# main35.net
KiCad netlist of a schematic drawn in EAGLE
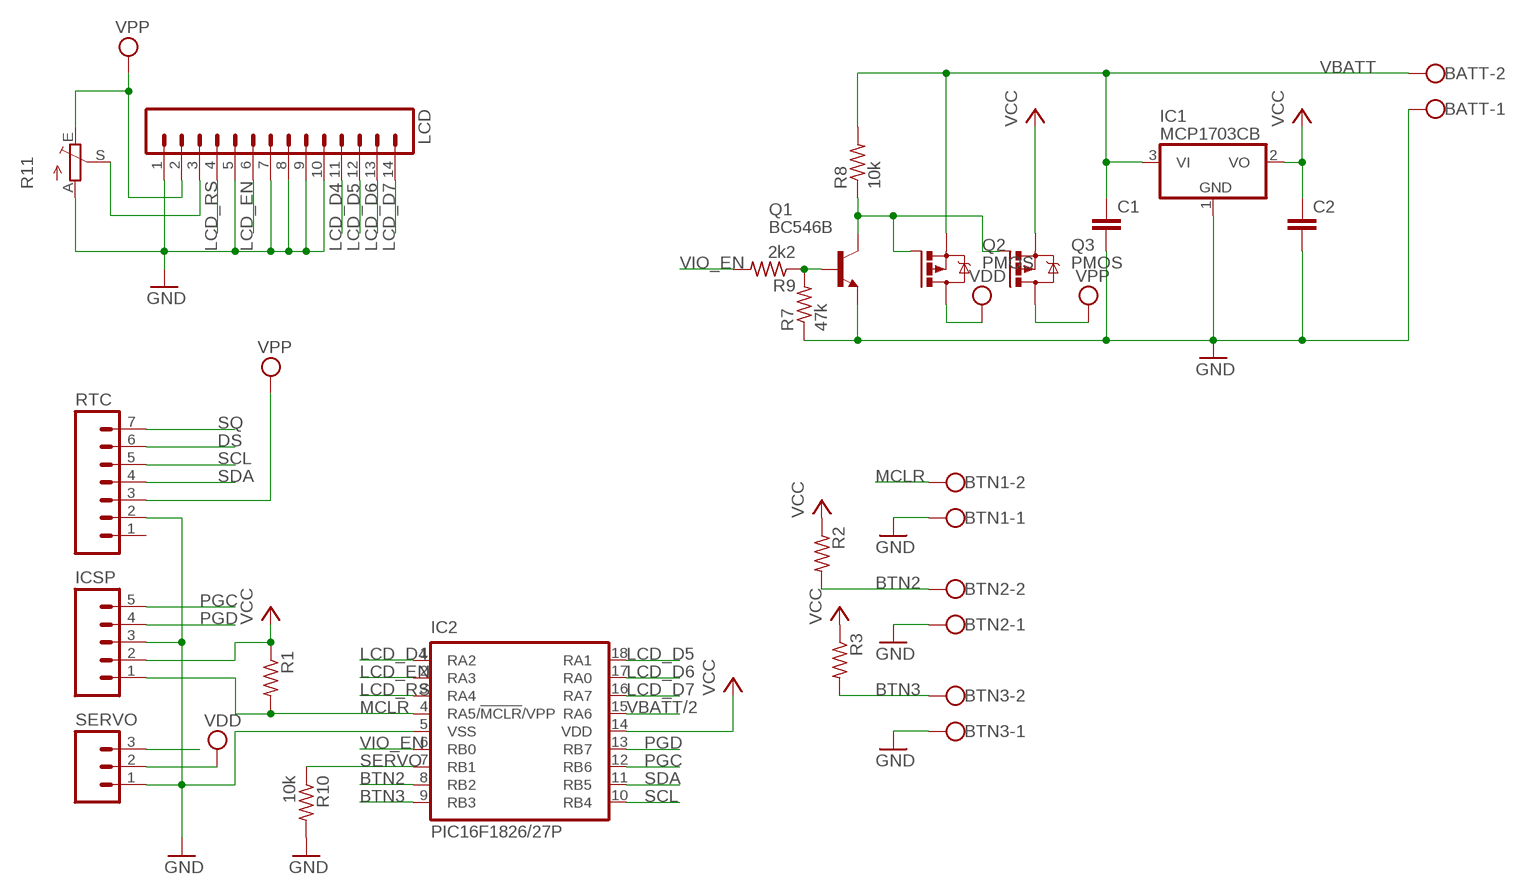
[diagram p0: schematic, sheet 1]

(export (version "E")
  (design (tool "Eeschema 10.0.6"))
  (components
    (comp (ref "BATT")
      (value "W237-102")
      (footprint "eagle-import:W237-102")
      (fields (field (name "MPN") "237-102"))
      (libsource (lib "eagle-import") (part "W237-102"))
    )
    (comp (ref "BTN1")
      (value "W237-102")
      (footprint "eagle-import:W237-102")
      (fields (field (name "MPN") "237-102"))
      (libsource (lib "eagle-import") (part "W237-102"))
    )
    (comp (ref "BTN2")
      (value "W237-102")
      (footprint "eagle-import:W237-102")
      (fields (field (name "MPN") "237-102"))
      (libsource (lib "eagle-import") (part "W237-102"))
    )
    (comp (ref "BTN3")
      (value "W237-102")
      (footprint "eagle-import:W237-102")
      (fields (field (name "MPN") "237-102"))
      (libsource (lib "eagle-import") (part "W237-102"))
    )
    (comp (ref "C1")
      (value "C-EUC0805K")
      (footprint "eagle-import:C0805K")
      (libsource (lib "eagle-import") (part "C-EUC0805K"))
    )
    (comp (ref "C2")
      (value "C-EUC0805K")
      (footprint "eagle-import:C0805K")
      (libsource (lib "eagle-import") (part "C-EUC0805K"))
    )
    (comp (ref "IC1")
      (value "MCP1703CB")
      (footprint "eagle-import:SOT23")
      (libsource (lib "eagle-import") (part "MCP1703CB"))
    )
    (comp (ref "IC2")
      (value "PIC16F1826/27P")
      (footprint "eagle-import:DIL18")
      (libsource (lib "eagle-import") (part "PIC16F1826/27P"))
    )
    (comp (ref "ICSP")
      (value "M05")
      (footprint "eagle-import:05P")
      (libsource (lib "eagle-import") (part "M05"))
    )
    (comp (ref "LCD")
      (value "M14")
      (footprint "eagle-import:14P")
      (libsource (lib "eagle-import") (part "M14"))
    )
    (comp (ref "Q1")
      (value "BC546B")
      (footprint "eagle-import:TO92-EBC")
      (libsource (lib "eagle-import") (part "BC546B"))
    )
    (comp (ref "Q2")
      (value "PMOS")
      (footprint "eagle-import:MICRO3")
      (libsource (lib "eagle-import") (part "IRLML5203"))
    )
    (comp (ref "Q3")
      (value "PMOS")
      (footprint "eagle-import:MICRO3")
      (libsource (lib "eagle-import") (part "IRLML5203"))
    )
    (comp (ref "R1")
      (value "R-US_M0805")
      (footprint "eagle-import:M0805")
      (libsource (lib "eagle-import") (part "R-US_M0805"))
    )
    (comp (ref "R2")
      (value "R-US_M0805")
      (footprint "eagle-import:M0805")
      (libsource (lib "eagle-import") (part "R-US_M0805"))
    )
    (comp (ref "R3")
      (value "R-US_M0805")
      (footprint "eagle-import:M0805")
      (libsource (lib "eagle-import") (part "R-US_M0805"))
    )
    (comp (ref "R7")
      (value "47k")
      (footprint "eagle-import:0207_10")
      (libsource (lib "eagle-import") (part "R-US_0207/10"))
    )
    (comp (ref "R8")
      (value "10k")
      (footprint "eagle-import:R1005")
      (libsource (lib "eagle-import") (part "R-US_R1005"))
    )
    (comp (ref "R9")
      (value "2k2")
      (footprint "eagle-import:0207_10")
      (libsource (lib "eagle-import") (part "R-US_0207/10"))
    )
    (comp (ref "R10")
      (value "10k")
      (footprint "eagle-import:R1005")
      (libsource (lib "eagle-import") (part "R-US_R1005"))
    )
    (comp (ref "R11")
      (value "TRIM_EU-LI10")
      (footprint "eagle-import:LI10")
      (libsource (lib "eagle-import") (part "TRIM_EU-LI10"))
    )
    (comp (ref "RTC")
      (value "M07")
      (footprint "eagle-import:07P")
      (libsource (lib "eagle-import") (part "M07"))
    )
    (comp (ref "SERVO")
      (value "M03")
      (footprint "eagle-import:03P")
      (libsource (lib "eagle-import") (part "M03"))
    )
  )
  (nets
    (net (code "1") (name "/BTN2") (class "Default")
      (node (ref "BTN2") (pin "2") (pinfunction "KL_2") (pintype "passive"))
      (node (ref "IC2") (pin "8") (pinfunction "RB2_8") (pintype "bidirectional"))
      (node (ref "R2") (pin "2") (pinfunction "2_2") (pintype "passive"))
    )
    (net (code "2") (name "/BTN3") (class "Default")
      (node (ref "BTN3") (pin "2") (pinfunction "KL_2") (pintype "passive"))
      (node (ref "IC2") (pin "9") (pinfunction "RB3_9") (pintype "bidirectional"))
      (node (ref "R3") (pin "2") (pinfunction "2_2") (pintype "passive"))
    )
    (net (code "3") (name "/DS") (class "Default")
      (node (ref "RTC") (pin "6") (pinfunction "6_6") (pintype "passive"))
    )
    (net (code "4") (name "/LCD_D4") (class "Default")
      (node (ref "IC2") (pin "1") (pinfunction "RA2_1") (pintype "bidirectional"))
      (node (ref "LCD") (pin "11") (pinfunction "11_11") (pintype "passive"))
    )
    (net (code "5") (name "/LCD_D5") (class "Default")
      (node (ref "IC2") (pin "18") (pinfunction "RA1_18") (pintype "bidirectional"))
      (node (ref "LCD") (pin "12") (pinfunction "12_12") (pintype "passive"))
    )
    (net (code "6") (name "/LCD_D6") (class "Default")
      (node (ref "IC2") (pin "17") (pinfunction "RA0_17") (pintype "bidirectional"))
      (node (ref "LCD") (pin "13") (pinfunction "13_13") (pintype "passive"))
    )
    (net (code "7") (name "/LCD_D7") (class "Default")
      (node (ref "IC2") (pin "16") (pinfunction "RA7_16") (pintype "bidirectional"))
      (node (ref "LCD") (pin "14") (pinfunction "14_14") (pintype "passive"))
    )
    (net (code "8") (name "/LCD_EN") (class "Default")
      (node (ref "IC2") (pin "2") (pinfunction "RA3_2") (pintype "bidirectional"))
      (node (ref "LCD") (pin "6") (pinfunction "6_6") (pintype "passive"))
    )
    (net (code "9") (name "/LCD_RS") (class "Default")
      (node (ref "IC2") (pin "3") (pinfunction "RA4_3") (pintype "bidirectional"))
      (node (ref "LCD") (pin "4") (pinfunction "4_4") (pintype "passive"))
    )
    (net (code "10") (name "/MCLR") (class "Default")
      (node (ref "BTN1") (pin "2") (pinfunction "KL_2") (pintype "passive"))
      (node (ref "IC2") (pin "4") (pinfunction "RA5/~{MCLR}/VPP_4") (pintype "bidirectional"))
      (node (ref "ICSP") (pin "1") (pinfunction "1_1") (pintype "passive"))
      (node (ref "R1") (pin "2") (pinfunction "2_2") (pintype "passive"))
    )
    (net (code "11") (name "/PGC") (class "Default")
      (node (ref "IC2") (pin "12") (pinfunction "RB6_12") (pintype "bidirectional"))
      (node (ref "ICSP") (pin "5") (pinfunction "5_5") (pintype "passive"))
    )
    (net (code "12") (name "/PGD") (class "Default")
      (node (ref "IC2") (pin "13") (pinfunction "RB7_13") (pintype "bidirectional"))
      (node (ref "ICSP") (pin "4") (pinfunction "4_4") (pintype "passive"))
    )
    (net (code "13") (name "/SCL") (class "Default")
      (node (ref "IC2") (pin "10") (pinfunction "RB4_10") (pintype "bidirectional"))
      (node (ref "RTC") (pin "5") (pinfunction "5_5") (pintype "passive"))
    )
    (net (code "14") (name "/SDA") (class "Default")
      (node (ref "IC2") (pin "11") (pinfunction "RB5_11") (pintype "bidirectional"))
      (node (ref "RTC") (pin "4") (pinfunction "4_4") (pintype "passive"))
    )
    (net (code "15") (name "/SERVO") (class "Default")
      (node (ref "IC2") (pin "7") (pinfunction "RB1_7") (pintype "bidirectional"))
      (node (ref "R10") (pin "1") (pinfunction "1_1") (pintype "passive"))
      (node (ref "SERVO") (pin "3") (pinfunction "3_3") (pintype "passive"))
    )
    (net (code "16") (name "/SQ") (class "Default")
      (node (ref "RTC") (pin "7") (pinfunction "7_7") (pintype "passive"))
    )
    (net (code "17") (name "/VBATT") (class "Default")
      (node (ref "BATT") (pin "2") (pinfunction "KL_2") (pintype "passive"))
      (node (ref "C1") (pin "1") (pinfunction "1_1") (pintype "passive"))
      (node (ref "IC1") (pin "3") (pinfunction "VI_3") (pintype "input"))
      (node (ref "Q2") (pin "2") (pinfunction "S_2") (pintype "passive"))
      (node (ref "R8") (pin "2") (pinfunction "2_2") (pintype "passive"))
    )
    (net (code "18") (name "/VBATT{slash}2") (class "Default")
      (node (ref "IC2") (pin "15") (pinfunction "RA6_15") (pintype "bidirectional"))
    )
    (net (code "19") (name "/VIO_EN") (class "Default")
      (node (ref "IC2") (pin "6") (pinfunction "RB0_6") (pintype "bidirectional"))
      (node (ref "R9") (pin "2") (pinfunction "2_2") (pintype "passive"))
    )
    (net (code "20") (name "GND") (class "Default")
      (node (ref "BATT") (pin "1") (pinfunction "KL_1") (pintype "passive"))
      (node (ref "BTN1") (pin "1") (pinfunction "KL_1") (pintype "passive"))
      (node (ref "BTN2") (pin "1") (pinfunction "KL_1") (pintype "passive"))
      (node (ref "BTN3") (pin "1") (pinfunction "KL_1") (pintype "passive"))
      (node (ref "C1") (pin "2") (pinfunction "2_2") (pintype "passive"))
      (node (ref "C2") (pin "2") (pinfunction "2_2") (pintype "passive"))
      (node (ref "IC1") (pin "1") (pinfunction "GND_1") (pintype "passive"))
      (node (ref "IC2") (pin "5") (pinfunction "VSS_5") (pintype "power_in"))
      (node (ref "ICSP") (pin "3") (pinfunction "3_3") (pintype "passive"))
      (node (ref "LCD") (pin "1") (pinfunction "1_1") (pintype "passive"))
      (node (ref "LCD") (pin "10") (pinfunction "10_10") (pintype "passive"))
      (node (ref "LCD") (pin "5") (pinfunction "5_5") (pintype "passive"))
      (node (ref "LCD") (pin "7") (pinfunction "7_7") (pintype "passive"))
      (node (ref "LCD") (pin "8") (pinfunction "8_8") (pintype "passive"))
      (node (ref "LCD") (pin "9") (pinfunction "9_9") (pintype "passive"))
      (node (ref "Q1") (pin "E") (pinfunction "E_E") (pintype "passive"))
      (node (ref "R10") (pin "2") (pinfunction "2_2") (pintype "passive"))
      (node (ref "R11") (pin "A") (pinfunction "A_A") (pintype "passive"))
      (node (ref "R7") (pin "1") (pinfunction "1_1") (pintype "passive"))
      (node (ref "RTC") (pin "2") (pinfunction "2_2") (pintype "passive"))
      (node (ref "SERVO") (pin "1") (pinfunction "1_1") (pintype "passive"))
    )
    (net (code "21") (name "Net-(LCD-Pad3)") (class "Default")
      (node (ref "LCD") (pin "3") (pinfunction "3_3") (pintype "passive"))
      (node (ref "R11") (pin "S") (pinfunction "S_S") (pintype "passive"))
    )
    (net (code "22") (name "Net-(Q1-PadB)") (class "Default")
      (node (ref "Q1") (pin "B") (pinfunction "B_B") (pintype "passive"))
      (node (ref "R7") (pin "2") (pinfunction "2_2") (pintype "passive"))
      (node (ref "R9") (pin "1") (pinfunction "1_1") (pintype "passive"))
    )
    (net (code "23") (name "Net-(Q2-G)") (class "Default")
      (node (ref "Q1") (pin "C") (pinfunction "C_C") (pintype "passive"))
      (node (ref "Q2") (pin "1") (pinfunction "G_1") (pintype "passive"))
      (node (ref "Q3") (pin "1") (pinfunction "G_1") (pintype "passive"))
      (node (ref "R8") (pin "1") (pinfunction "1_1") (pintype "passive"))
    )
    (net (code "24") (name "VCC") (class "Default")
      (node (ref "C2") (pin "1") (pinfunction "1_1") (pintype "passive"))
      (node (ref "IC1") (pin "2") (pinfunction "VO_2") (pintype "passive"))
      (node (ref "IC2") (pin "14") (pinfunction "VDD_14") (pintype "power_in"))
      (node (ref "ICSP") (pin "2") (pinfunction "2_2") (pintype "passive"))
      (node (ref "Q3") (pin "2") (pinfunction "S_2") (pintype "passive"))
      (node (ref "R1") (pin "1") (pinfunction "1_1") (pintype "passive"))
      (node (ref "R2") (pin "1") (pinfunction "1_1") (pintype "passive"))
      (node (ref "R3") (pin "1") (pinfunction "1_1") (pintype "passive"))
    )
    (net (code "25") (name "VDD") (class "Default")
      (node (ref "Q2") (pin "3") (pinfunction "D_3") (pintype "passive"))
      (node (ref "SERVO") (pin "2") (pinfunction "2_2") (pintype "passive"))
    )
    (net (code "26") (name "VPP") (class "Default")
      (node (ref "LCD") (pin "2") (pinfunction "2_2") (pintype "passive"))
      (node (ref "Q3") (pin "3") (pinfunction "D_3") (pintype "passive"))
      (node (ref "R11") (pin "E") (pinfunction "E_E") (pintype "passive"))
      (node (ref "RTC") (pin "3") (pinfunction "3_3") (pintype "passive"))
    )
    (net (code "27") (name "unconnected-(RTC-Pad1)") (class "Default")
      (node (ref "RTC") (pin "1") (pinfunction "1_1") (pintype "passive"))
    )
  )
)
